# Tricorder-BoosterPack.net
KiCad netlist of a schematic drawn in EAGLE
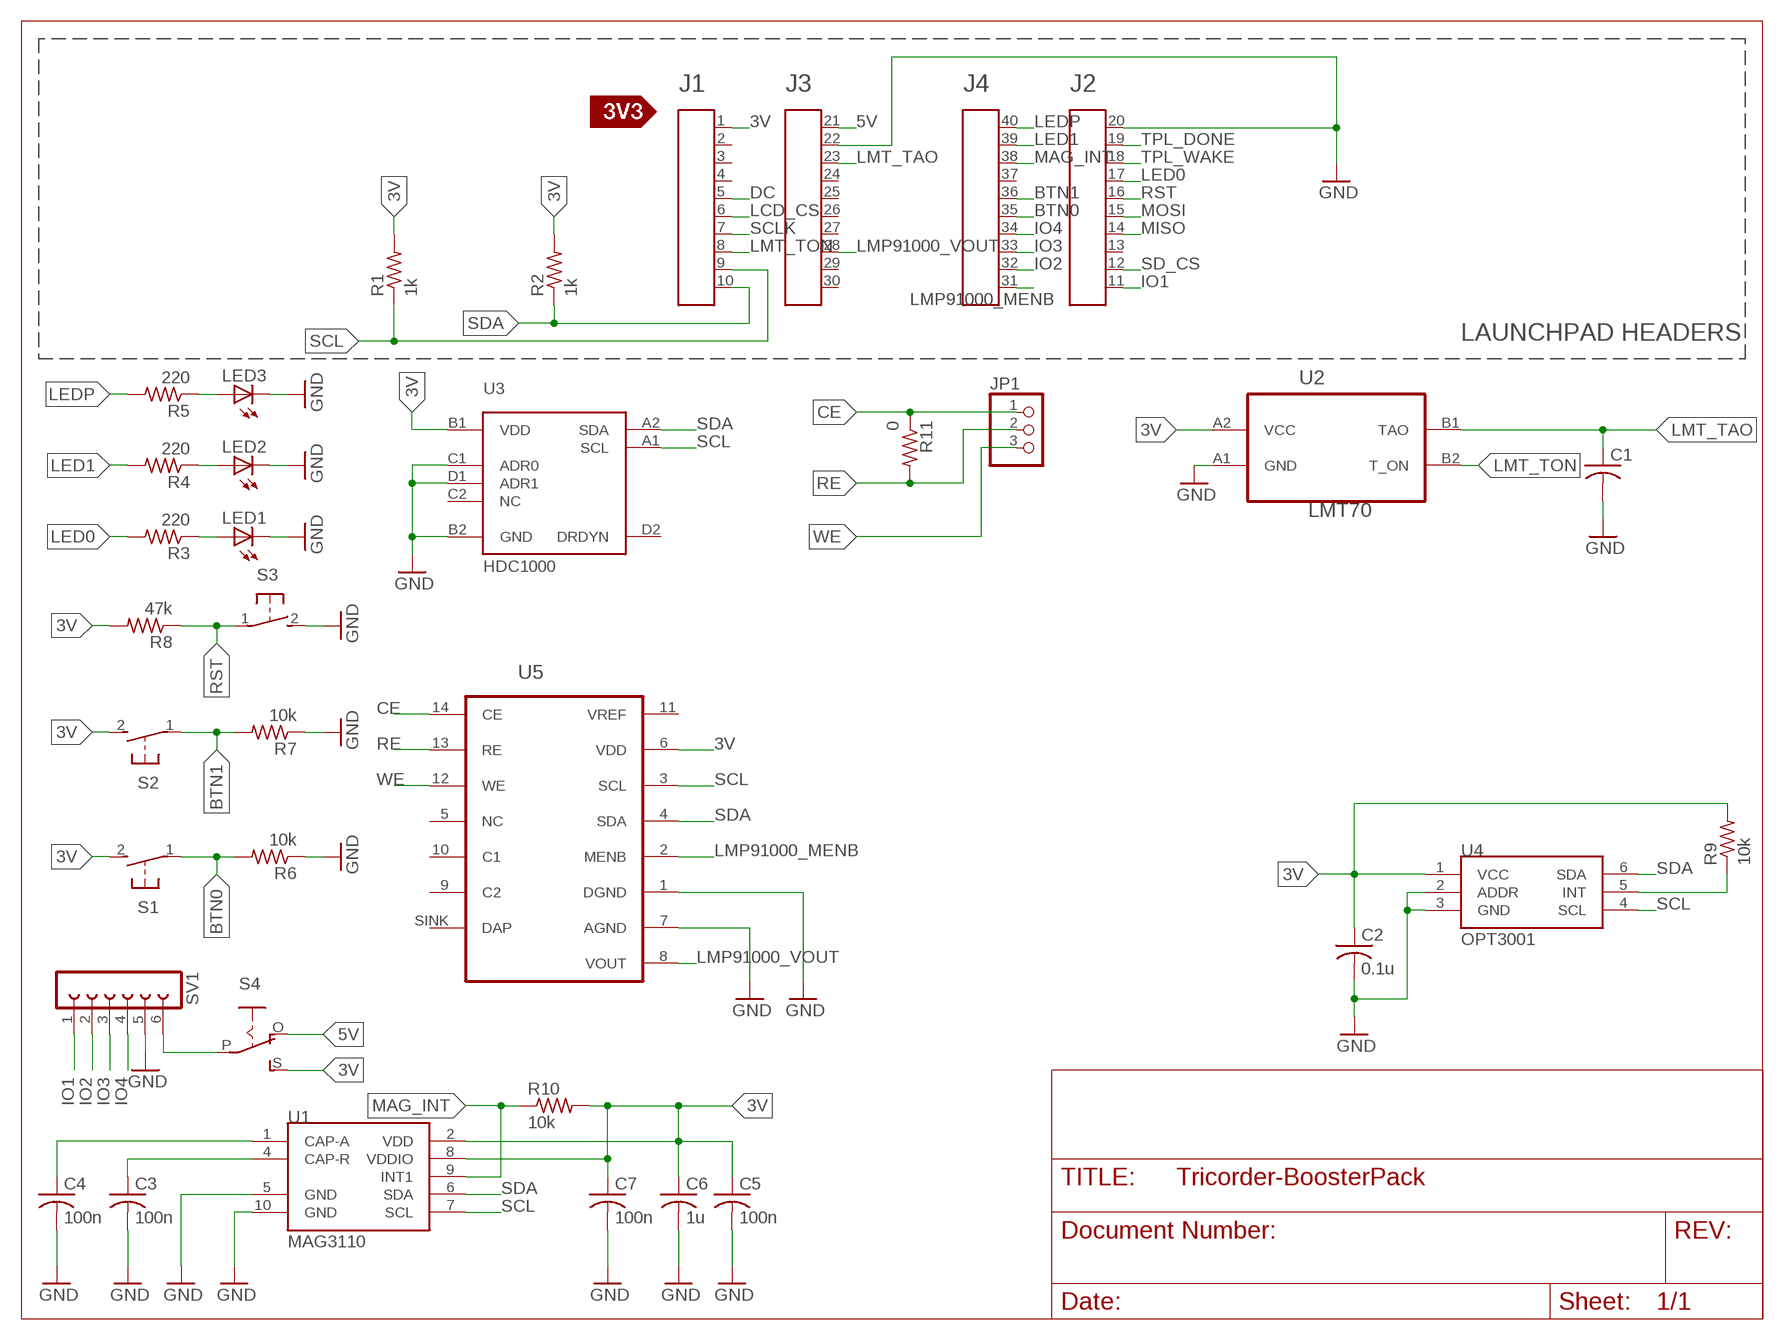
[diagram p0: schematic, sheet 1]

(export (version "E")
  (design (tool "Eeschema 10.0.6"))
  (components
    (comp (ref "A1")
      (value "HEADER4X10-BOOSTERPACK")
      (footprint "eagle-import:4X10-BOOSTERPACK")
      (libsource (lib "eagle-import") (part "HEADER4X10-BOOSTERPACK"))
    )
    (comp (ref "C1")
      (value "C-USC0603")
      (footprint "eagle-import:C0603")
      (libsource (lib "eagle-import") (part "C-USC0603"))
    )
    (comp (ref "C2")
      (value "0.1u")
      (footprint "eagle-import:C0603")
      (libsource (lib "eagle-import") (part "C-USC0603"))
    )
    (comp (ref "C3")
      (value "100n")
      (footprint "eagle-import:C0603")
      (libsource (lib "eagle-import") (part "C-USC0603"))
    )
    (comp (ref "C4")
      (value "100n")
      (footprint "eagle-import:C0603")
      (libsource (lib "eagle-import") (part "C-USC0603"))
    )
    (comp (ref "C5")
      (value "100n")
      (footprint "eagle-import:C0603")
      (libsource (lib "eagle-import") (part "C-USC0603"))
    )
    (comp (ref "C6")
      (value "1u")
      (footprint "eagle-import:C0603")
      (libsource (lib "eagle-import") (part "C-USC0603"))
    )
    (comp (ref "C7")
      (value "100n")
      (footprint "eagle-import:C0603")
      (libsource (lib "eagle-import") (part "C-USC0603"))
    )
    (comp (ref "JP1")
      (value "PINHD-1X3CB")
      (footprint "eagle-import:1X03-CLEANBIG")
      (libsource (lib "eagle-import") (part "PINHD-1X3CB"))
    )
    (comp (ref "LED1")
      (value "LEDCHIPLED_0603")
      (footprint "eagle-import:CHIPLED_0603")
      (libsource (lib "eagle-import") (part "LEDCHIPLED_0603"))
    )
    (comp (ref "LED2")
      (value "LEDCHIPLED_0603")
      (footprint "eagle-import:CHIPLED_0603")
      (libsource (lib "eagle-import") (part "LEDCHIPLED_0603"))
    )
    (comp (ref "LED3")
      (value "LEDCHIPLED_0603")
      (footprint "eagle-import:CHIPLED_0603")
      (libsource (lib "eagle-import") (part "LEDCHIPLED_0603"))
    )
    (comp (ref "R1")
      (value "1k")
      (footprint "eagle-import:R0603")
      (libsource (lib "eagle-import") (part "R-US_R0603"))
    )
    (comp (ref "R2")
      (value "1k")
      (footprint "eagle-import:R0603")
      (libsource (lib "eagle-import") (part "R-US_R0603"))
    )
    (comp (ref "R3")
      (value "220")
      (footprint "eagle-import:R0603")
      (libsource (lib "eagle-import") (part "R-US_R0603"))
    )
    (comp (ref "R4")
      (value "220")
      (footprint "eagle-import:R0603")
      (libsource (lib "eagle-import") (part "R-US_R0603"))
    )
    (comp (ref "R5")
      (value "220")
      (footprint "eagle-import:R0603")
      (libsource (lib "eagle-import") (part "R-US_R0603"))
    )
    (comp (ref "R6")
      (value "10k")
      (footprint "eagle-import:R0603")
      (libsource (lib "eagle-import") (part "R-US_R0603"))
    )
    (comp (ref "R7")
      (value "10k")
      (footprint "eagle-import:R0603")
      (libsource (lib "eagle-import") (part "R-US_R0603"))
    )
    (comp (ref "R8")
      (value "47k")
      (footprint "eagle-import:R0603")
      (libsource (lib "eagle-import") (part "R-US_R0603"))
    )
    (comp (ref "R9")
      (value "10k")
      (footprint "eagle-import:R0603")
      (libsource (lib "eagle-import") (part "R-US_R0603"))
    )
    (comp (ref "R10")
      (value "10k")
      (footprint "eagle-import:R0603")
      (libsource (lib "eagle-import") (part "R-US_R0603"))
    )
    (comp (ref "R11")
      (value "0")
      (footprint "eagle-import:R0603")
      (libsource (lib "eagle-import") (part "R-US_R0603"))
    )
    (comp (ref "S1")
      (value "31-XX")
      (footprint "eagle-import:B3F-31XX")
      (libsource (lib "eagle-import") (part "31-XX"))
    )
    (comp (ref "S2")
      (value "31-XX")
      (footprint "eagle-import:B3F-31XX")
      (libsource (lib "eagle-import") (part "31-XX"))
    )
    (comp (ref "S3")
      (value "31-XX")
      (footprint "eagle-import:B3F-31XX")
      (libsource (lib "eagle-import") (part "31-XX"))
    )
    (comp (ref "S4")
      (value "EG1218S")
      (footprint "eagle-import:EG1218")
      (libsource (lib "eagle-import") (part "EG1218S"))
    )
    (comp (ref "SV1")
      (value "FE06-1")
      (footprint "eagle-import:FE06")
      (libsource (lib "eagle-import") (part "FE06-1"))
    )
    (comp (ref "U$3")
      (value "SILK_3V3_TAG")
      (footprint "eagle-import:SILK_3V3_TAG")
      (libsource (lib "eagle-import") (part "SILK_3V3_TAG"))
    )
    (comp (ref "U1")
      (value "MAG3110")
      (footprint "eagle-import:DFN-10")
      (libsource (lib "eagle-import") (part "MAG3110"))
    )
    (comp (ref "U2")
      (value "LMT70LMT70")
      (footprint "eagle-import:BGA4C40P2X2_77X77X50")
      (fields (field (name "MPN") "LMT70"))
      (libsource (lib "eagle-import") (part "LMT70LMT70"))
    )
    (comp (ref "U3")
      (value "HDC1000")
      (footprint "eagle-import:DSBGA_8_YPA")
      (libsource (lib "eagle-import") (part "HDC1000"))
    )
    (comp (ref "U4")
      (value "OPT3001")
      (footprint "eagle-import:SOT23-6")
      (libsource (lib "eagle-import") (part "OPT3001"))
    )
    (comp (ref "U5")
      (value "LMP91000")
      (footprint "eagle-import:WFDFN-14")
      (libsource (lib "eagle-import") (part "LMP91000"))
    )
  )
  (nets
    (net (code "1") (name "/DC") (class "Default")
      (node (ref "A1") (pin "5") (pinfunction "P$5_5") (pintype "bidirectional"))
    )
    (net (code "2") (name "/IO1") (class "Default")
      (node (ref "A1") (pin "11") (pinfunction "P$11_11") (pintype "bidirectional"))
      (node (ref "SV1") (pin "1") (pinfunction "1_1") (pintype "passive"))
    )
    (net (code "3") (name "/IO2") (class "Default")
      (node (ref "A1") (pin "32") (pinfunction "P$32_32") (pintype "bidirectional"))
      (node (ref "SV1") (pin "2") (pinfunction "2_2") (pintype "passive"))
    )
    (net (code "4") (name "/IO3") (class "Default")
      (node (ref "A1") (pin "33") (pinfunction "P$33_33") (pintype "bidirectional"))
      (node (ref "SV1") (pin "3") (pinfunction "3_3") (pintype "passive"))
    )
    (net (code "5") (name "/IO4") (class "Default")
      (node (ref "A1") (pin "34") (pinfunction "P$34_34") (pintype "bidirectional"))
      (node (ref "SV1") (pin "4") (pinfunction "4_4") (pintype "passive"))
    )
    (net (code "6") (name "/LCD_CS") (class "Default")
      (node (ref "A1") (pin "6") (pinfunction "P$6_6") (pintype "bidirectional"))
    )
    (net (code "7") (name "/LMP91000_MENB") (class "Default")
      (node (ref "A1") (pin "31") (pinfunction "P$31_31") (pintype "bidirectional"))
      (node (ref "U5") (pin "2") (pinfunction "MENB_2") (pintype "passive"))
    )
    (net (code "8") (name "/LMP91000_VOUT") (class "Default")
      (node (ref "A1") (pin "28") (pinfunction "P$28_28") (pintype "bidirectional"))
      (node (ref "U5") (pin "8") (pinfunction "VOUT_8") (pintype "passive"))
    )
    (net (code "9") (name "/MISO") (class "Default")
      (node (ref "A1") (pin "14") (pinfunction "P$14_14") (pintype "bidirectional"))
    )
    (net (code "10") (name "/MOSI") (class "Default")
      (node (ref "A1") (pin "15") (pinfunction "P$15_15") (pintype "bidirectional"))
    )
    (net (code "11") (name "/SCLK") (class "Default")
      (node (ref "A1") (pin "7") (pinfunction "P$7_7") (pintype "bidirectional"))
    )
    (net (code "12") (name "/SD_CS") (class "Default")
      (node (ref "A1") (pin "12") (pinfunction "P$12_12") (pintype "bidirectional"))
    )
    (net (code "13") (name "/TPL_DONE") (class "Default")
      (node (ref "A1") (pin "19") (pinfunction "P$19_19") (pintype "bidirectional"))
    )
    (net (code "14") (name "/TPL_WAKE") (class "Default")
      (node (ref "A1") (pin "18") (pinfunction "P$18_18") (pintype "bidirectional"))
    )
    (net (code "15") (name "/VREF") (class "Default")
      (node (ref "U5") (pin "11") (pinfunction "VREF_11") (pintype "power_in"))
    )
    (net (code "16") (name "3V") (class "Default")
      (node (ref "A1") (pin "1") (pinfunction "P$1_1") (pintype "bidirectional"))
      (node (ref "C2") (pin "1") (pinfunction "1_1") (pintype "passive"))
      (node (ref "R1") (pin "2") (pinfunction "2_2") (pintype "passive"))
      (node (ref "R2") (pin "2") (pinfunction "2_2") (pintype "passive"))
      (node (ref "R8") (pin "2") (pinfunction "2_2") (pintype "passive"))
      (node (ref "R9") (pin "2") (pinfunction "2_2") (pintype "passive"))
      (node (ref "S1") (pin "2") (pinfunction "S_2") (pintype "passive"))
      (node (ref "S2") (pin "2") (pinfunction "S_2") (pintype "passive"))
      (node (ref "S4") (pin "S") (pinfunction "S_S") (pintype "passive"))
      (node (ref "U3") (pin "B1") (pinfunction "VDD_B1") (pintype "power_in"))
      (node (ref "U4") (pin "1") (pinfunction "VCC_1") (pintype "power_in"))
      (node (ref "U5") (pin "6") (pinfunction "VDD_6") (pintype "power_in"))
    )
    (net (code "17") (name "5V") (class "Default")
      (node (ref "A1") (pin "21") (pinfunction "P$21_21") (pintype "bidirectional"))
      (node (ref "S4") (pin "O") (pinfunction "O_O") (pintype "passive"))
    )
    (net (code "18") (name "BTN0") (class "Default")
      (node (ref "A1") (pin "35") (pinfunction "P$35_35") (pintype "bidirectional"))
      (node (ref "R6") (pin "2") (pinfunction "2_2") (pintype "passive"))
      (node (ref "S1") (pin "1") (pinfunction "P_1") (pintype "passive"))
    )
    (net (code "19") (name "BTN1") (class "Default")
      (node (ref "A1") (pin "36") (pinfunction "P$36_36") (pintype "bidirectional"))
      (node (ref "R7") (pin "2") (pinfunction "2_2") (pintype "passive"))
      (node (ref "S2") (pin "1") (pinfunction "P_1") (pintype "passive"))
    )
    (net (code "20") (name "CE") (class "Default")
      (node (ref "JP1") (pin "1") (pinfunction "1_1") (pintype "passive"))
      (node (ref "R11") (pin "1") (pinfunction "1_1") (pintype "passive"))
      (node (ref "U5") (pin "14") (pinfunction "CE_14") (pintype "bidirectional"))
    )
    (net (code "21") (name "GND") (class "Default")
      (node (ref "A1") (pin "20") (pinfunction "P$20_20") (pintype "bidirectional"))
      (node (ref "A1") (pin "22") (pinfunction "P$22_22") (pintype "bidirectional"))
      (node (ref "C1") (pin "2") (pinfunction "2_2") (pintype "passive"))
      (node (ref "C2") (pin "2") (pinfunction "2_2") (pintype "passive"))
      (node (ref "C3") (pin "2") (pinfunction "2_2") (pintype "passive"))
      (node (ref "C4") (pin "2") (pinfunction "2_2") (pintype "passive"))
      (node (ref "C5") (pin "2") (pinfunction "2_2") (pintype "passive"))
      (node (ref "C6") (pin "2") (pinfunction "2_2") (pintype "passive"))
      (node (ref "C7") (pin "2") (pinfunction "2_2") (pintype "passive"))
      (node (ref "LED1") (pin "C") (pinfunction "C_C") (pintype "passive"))
      (node (ref "LED2") (pin "C") (pinfunction "C_C") (pintype "passive"))
      (node (ref "LED3") (pin "C") (pinfunction "C_C") (pintype "passive"))
      (node (ref "R6") (pin "1") (pinfunction "1_1") (pintype "passive"))
      (node (ref "R7") (pin "1") (pinfunction "1_1") (pintype "passive"))
      (node (ref "S3") (pin "2") (pinfunction "S_2") (pintype "passive"))
      (node (ref "SV1") (pin "5") (pinfunction "5_5") (pintype "passive"))
      (node (ref "U1") (pin "10") (pinfunction "GND_10") (pintype "bidirectional"))
      (node (ref "U1") (pin "5") (pinfunction "GND_5") (pintype "bidirectional"))
      (node (ref "U2") (pin "A1") (pinfunction "GND_A1") (pintype "passive"))
      (node (ref "U3") (pin "B2") (pinfunction "GND_B2") (pintype "power_in"))
      (node (ref "U3") (pin "C1") (pinfunction "ADR0_C1") (pintype "input"))
      (node (ref "U3") (pin "D1") (pinfunction "ADR1_D1") (pintype "input"))
      (node (ref "U4") (pin "2") (pinfunction "ADDR_2") (pintype "input"))
      (node (ref "U4") (pin "3") (pinfunction "GND_3") (pintype "power_in"))
      (node (ref "U5") (pin "1") (pinfunction "DGND_1") (pintype "passive"))
      (node (ref "U5") (pin "7") (pinfunction "AGND_7") (pintype "passive"))
    )
    (net (code "22") (name "LED0") (class "Default")
      (node (ref "A1") (pin "17") (pinfunction "P$17_17") (pintype "bidirectional"))
      (node (ref "R3") (pin "2") (pinfunction "2_2") (pintype "passive"))
    )
    (net (code "23") (name "LED1") (class "Default")
      (node (ref "A1") (pin "39") (pinfunction "P$39_39") (pintype "bidirectional"))
      (node (ref "R4") (pin "2") (pinfunction "2_2") (pintype "passive"))
    )
    (net (code "24") (name "LEDP") (class "Default")
      (node (ref "A1") (pin "40") (pinfunction "P$40_40") (pintype "bidirectional"))
      (node (ref "R5") (pin "2") (pinfunction "2_2") (pintype "passive"))
    )
    (net (code "25") (name "LMT_TAO") (class "Default")
      (node (ref "A1") (pin "23") (pinfunction "P$23_23") (pintype "bidirectional"))
      (node (ref "C1") (pin "1") (pinfunction "1_1") (pintype "passive"))
      (node (ref "U2") (pin "B1") (pinfunction "TAO_B1") (pintype "output"))
    )
    (net (code "26") (name "LMT_TON") (class "Default")
      (node (ref "A1") (pin "8") (pinfunction "P$8_8") (pintype "bidirectional"))
      (node (ref "U2") (pin "B2") (pinfunction "T_ON_B2") (pintype "input"))
    )
    (net (code "27") (name "MAG_INT") (class "Default")
      (node (ref "A1") (pin "38") (pinfunction "P$38_38") (pintype "bidirectional"))
      (node (ref "R10") (pin "1") (pinfunction "1_1") (pintype "passive"))
      (node (ref "U1") (pin "9") (pinfunction "INT1_9") (pintype "bidirectional"))
    )
    (net (code "28") (name "Net-(LED1-PadA)") (class "Default")
      (node (ref "LED1") (pin "A") (pinfunction "A_A") (pintype "passive"))
      (node (ref "R3") (pin "1") (pinfunction "1_1") (pintype "passive"))
    )
    (net (code "29") (name "Net-(LED2-PadA)") (class "Default")
      (node (ref "LED2") (pin "A") (pinfunction "A_A") (pintype "passive"))
      (node (ref "R4") (pin "1") (pinfunction "1_1") (pintype "passive"))
    )
    (net (code "30") (name "Net-(LED3-PadA)") (class "Default")
      (node (ref "LED3") (pin "A") (pinfunction "A_A") (pintype "passive"))
      (node (ref "R5") (pin "1") (pinfunction "1_1") (pintype "passive"))
    )
    (net (code "31") (name "Net-(S4-PadP)") (class "Default")
      (node (ref "S4") (pin "P") (pinfunction "P_P") (pintype "passive"))
      (node (ref "SV1") (pin "6") (pinfunction "6_6") (pintype "passive"))
    )
    (net (code "32") (name "Net-(U1-CAP-A)") (class "Default")
      (node (ref "C4") (pin "1") (pinfunction "1_1") (pintype "passive"))
      (node (ref "U1") (pin "1") (pinfunction "CAP-A_1") (pintype "bidirectional"))
    )
    (net (code "33") (name "Net-(U1-CAP-R)") (class "Default")
      (node (ref "C3") (pin "1") (pinfunction "1_1") (pintype "passive"))
      (node (ref "U1") (pin "4") (pinfunction "CAP-R_4") (pintype "bidirectional"))
    )
    (net (code "34") (name "Net-(U1-VDD)") (class "Default")
      (node (ref "C5") (pin "1") (pinfunction "1_1") (pintype "passive"))
      (node (ref "C6") (pin "1") (pinfunction "1_1") (pintype "passive"))
      (node (ref "C7") (pin "1") (pinfunction "1_1") (pintype "passive"))
      (node (ref "R10") (pin "2") (pinfunction "2_2") (pintype "passive"))
      (node (ref "U1") (pin "2") (pinfunction "VDD_2") (pintype "bidirectional"))
      (node (ref "U1") (pin "8") (pinfunction "VDDIO_8") (pintype "bidirectional"))
    )
    (net (code "35") (name "Net-(U4-INT)") (class "Default")
      (node (ref "R9") (pin "1") (pinfunction "1_1") (pintype "passive"))
      (node (ref "U4") (pin "5") (pinfunction "INT_5") (pintype "output"))
    )
    (net (code "36") (name "RE") (class "Default")
      (node (ref "JP1") (pin "2") (pinfunction "2_2") (pintype "passive"))
      (node (ref "R11") (pin "2") (pinfunction "2_2") (pintype "passive"))
      (node (ref "U5") (pin "13") (pinfunction "RE_13") (pintype "bidirectional"))
    )
    (net (code "37") (name "RST") (class "Default")
      (node (ref "A1") (pin "16") (pinfunction "P$16_16") (pintype "bidirectional"))
      (node (ref "R8") (pin "1") (pinfunction "1_1") (pintype "passive"))
      (node (ref "S3") (pin "1") (pinfunction "P_1") (pintype "passive"))
    )
    (net (code "38") (name "SCL") (class "Default")
      (node (ref "A1") (pin "9") (pinfunction "P$9_9") (pintype "bidirectional"))
      (node (ref "R1") (pin "1") (pinfunction "1_1") (pintype "passive"))
      (node (ref "U1") (pin "7") (pinfunction "SCL_7") (pintype "bidirectional"))
      (node (ref "U3") (pin "A1") (pinfunction "SCL_A1") (pintype "input"))
      (node (ref "U4") (pin "4") (pinfunction "SCL_4") (pintype "input"))
      (node (ref "U5") (pin "3") (pinfunction "SCL_3") (pintype "bidirectional"))
    )
    (net (code "39") (name "SDA") (class "Default")
      (node (ref "A1") (pin "10") (pinfunction "P$10_10") (pintype "bidirectional"))
      (node (ref "R2") (pin "1") (pinfunction "1_1") (pintype "passive"))
      (node (ref "U1") (pin "6") (pinfunction "SDA_6") (pintype "bidirectional"))
      (node (ref "U3") (pin "A2") (pinfunction "SDA_A2") (pintype "bidirectional"))
      (node (ref "U4") (pin "6") (pinfunction "SDA_6") (pintype "input"))
      (node (ref "U5") (pin "4") (pinfunction "SDA_4") (pintype "passive"))
    )
    (net (code "40") (name "WE") (class "Default")
      (node (ref "JP1") (pin "3") (pinfunction "3_3") (pintype "passive"))
      (node (ref "U5") (pin "12") (pinfunction "WE_12") (pintype "bidirectional"))
    )
    (net (code "41") (name "unconnected-(A1-P$2-Pad2)") (class "Default")
      (node (ref "A1") (pin "2") (pinfunction "P$2_2") (pintype "bidirectional"))
    )
    (net (code "42") (name "unconnected-(A1-P$3-Pad3)") (class "Default")
      (node (ref "A1") (pin "3") (pinfunction "P$3_3") (pintype "bidirectional"))
    )
    (net (code "43") (name "unconnected-(A1-P$4-Pad4)") (class "Default")
      (node (ref "A1") (pin "4") (pinfunction "P$4_4") (pintype "bidirectional"))
    )
    (net (code "44") (name "unconnected-(A1-P$13-Pad13)") (class "Default")
      (node (ref "A1") (pin "13") (pinfunction "P$13_13") (pintype "bidirectional"))
    )
    (net (code "45") (name "unconnected-(A1-P$24-Pad24)") (class "Default")
      (node (ref "A1") (pin "24") (pinfunction "P$24_24") (pintype "bidirectional"))
    )
    (net (code "46") (name "unconnected-(A1-P$25-Pad25)") (class "Default")
      (node (ref "A1") (pin "25") (pinfunction "P$25_25") (pintype "bidirectional"))
    )
    (net (code "47") (name "unconnected-(A1-P$26-Pad26)") (class "Default")
      (node (ref "A1") (pin "26") (pinfunction "P$26_26") (pintype "bidirectional"))
    )
    (net (code "48") (name "unconnected-(A1-P$27-Pad27)") (class "Default")
      (node (ref "A1") (pin "27") (pinfunction "P$27_27") (pintype "bidirectional"))
    )
    (net (code "49") (name "unconnected-(A1-P$29-Pad29)") (class "Default")
      (node (ref "A1") (pin "29") (pinfunction "P$29_29") (pintype "bidirectional"))
    )
    (net (code "50") (name "unconnected-(A1-P$30-Pad30)") (class "Default")
      (node (ref "A1") (pin "30") (pinfunction "P$30_30") (pintype "bidirectional"))
    )
    (net (code "51") (name "unconnected-(A1-P$37-Pad37)") (class "Default")
      (node (ref "A1") (pin "37") (pinfunction "P$37_37") (pintype "bidirectional"))
    )
    (net (code "52") (name "unconnected-(U2-VCC-PadA2)") (class "Default")
      (node (ref "U2") (pin "A2") (pinfunction "VCC_A2") (pintype "power_in"))
    )
    (net (code "53") (name "unconnected-(U3-DRDYN-PadD2)") (class "Default")
      (node (ref "U3") (pin "D2") (pinfunction "DRDYN_D2") (pintype "output"))
    )
    (net (code "54") (name "unconnected-(U3-NC-PadC2)") (class "Default")
      (node (ref "U3") (pin "C2") (pinfunction "NC_C2") (pintype "no_connect"))
    )
    (net (code "55") (name "unconnected-(U5-C1-Pad10)") (class "Default")
      (node (ref "U5") (pin "10") (pinfunction "C1_10") (pintype "passive"))
    )
    (net (code "56") (name "unconnected-(U5-C2-Pad9)") (class "Default")
      (node (ref "U5") (pin "9") (pinfunction "C2_9") (pintype "passive"))
    )
    (net (code "57") (name "unconnected-(U5-DAP-PadSINK)") (class "Default")
      (node (ref "U5") (pin "SINK") (pinfunction "DAP_SINK") (pintype "passive"))
    )
    (net (code "58") (name "unconnected-(U5-NC-Pad5)") (class "Default")
      (node (ref "U5") (pin "5") (pinfunction "NC_5") (pintype "passive"))
    )
  )
)
